# USB.net
KiCad netlist of a schematic drawn in Altium Designer
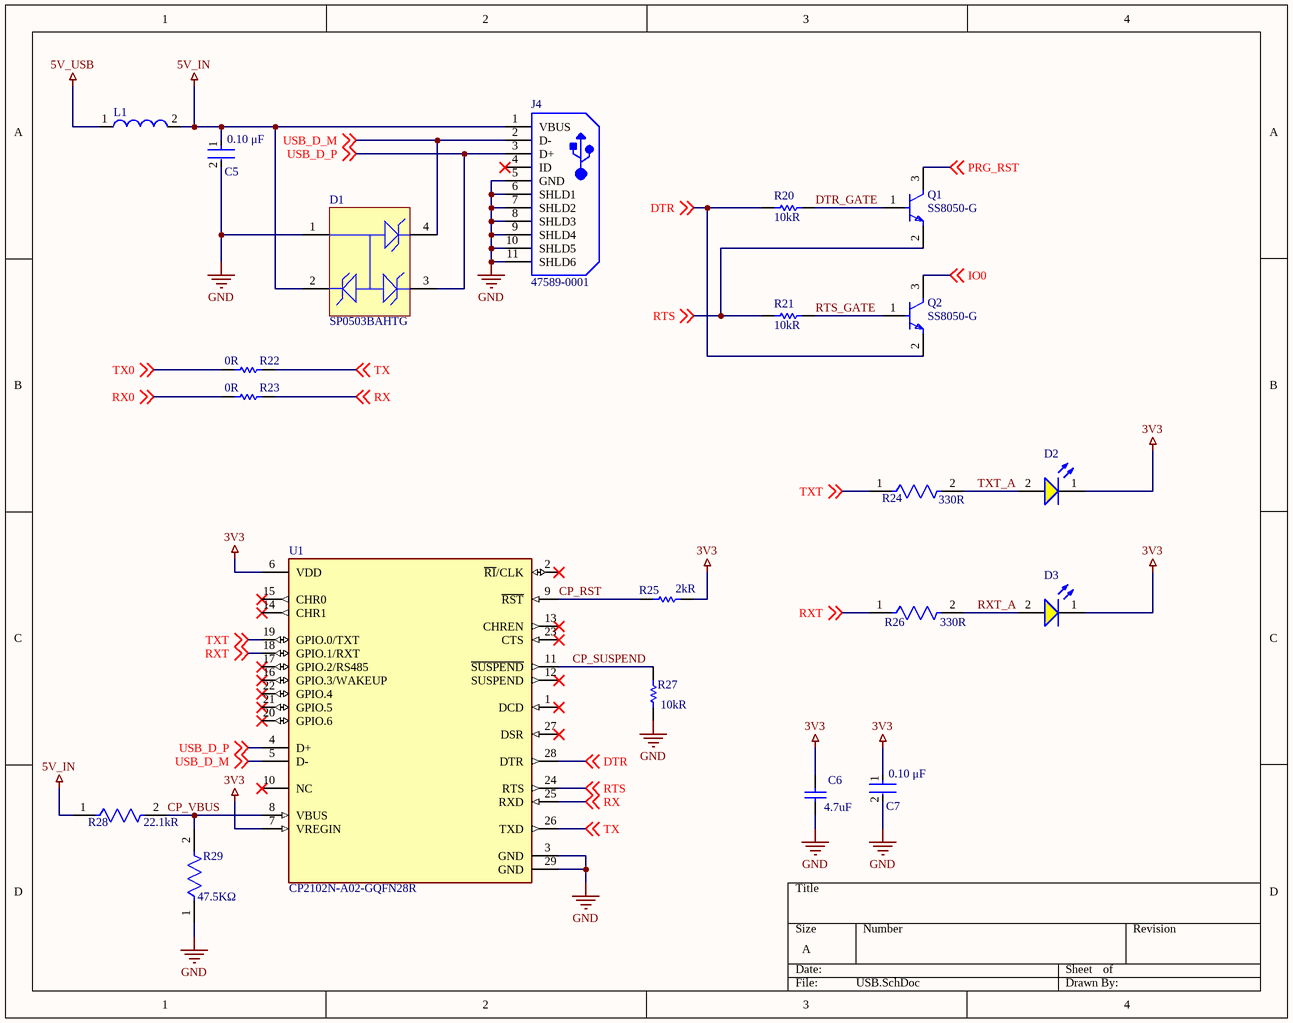
[diagram p0: USB.SchDoc]

(export (version "E")
  (design (tool "Eeschema 10.0.6"))
  (components
    (comp (ref "C5")
      (value "0.10 μF")
      (footprint "FP-C1206C-EB-MFG")
      (description "CAP CER 0.1UF 100V X7R 1206")
      (fields
        (field (name "TOLERANCE") "0.1")
        (field (name "OCTOPART") "https://octopart.com/c1206c104k1ractu-kemet-89521")
      )
      (libsource (lib "Altium Content Vault") (part "b4654b650e69147ec39a6b967a45e02"))
    )
    (comp (ref "C6")
      (value "4.7uF")
      (footprint "CAPC1210(3225)220_M")
      (description "CAP 4.7uF 25V ±10% 1210 (3225 Metric) Thickness 2.2mm SMD")
      (fields (field (name "TOLERANCE") "Â±10%") (field (name "MANUFACTURER") "KEMET"))
      (libsource (lib "Altium Content Vault") (part "CAP"))
    )
    (comp (ref "C7")
      (value "0.10 μF")
      (footprint "FP-C1206C-EB-MFG")
      (description "CAP CER 0.1UF 100V X7R 1206")
      (fields
        (field (name "TOLERANCE") "0.1")
        (field (name "OCTOPART") "https://octopart.com/c1206c104k1ractu-kemet-89521")
      )
      (libsource (lib "Altium Content Vault") (part "b4654b650e69147ec39a6b967a45e02"))
    )
    (comp (ref "D1")
      (value "SP0503BAHTG")
      (footprint "LFUS-SOT143-4_V")
      (description "TVS Diode Array, 30 pF, 30 KV, -40 to 85 degC, 4-Pin SOT143, RoHS, Tape and Reel")
      (fields (field (name "MANUFACTURER") "Littelfuse"))
      (libsource (lib "Altium Content Vault") (part "LFUS-SP0503BAHTG-SOT143-4"))
    )
    (comp (ref "D2")
      (value "150080YS75000")
      (footprint "WL-SMCW_0805_150080xx75000")
      (fields (field (name "MANUFACTURER") "Wurth Electronics"))
      (libsource (lib "Altium Content Vault") (part "LED_Yellow_2A-1K"))
    )
    (comp (ref "D3")
      (value "150080YS75000")
      (footprint "WL-SMCW_0805_150080xx75000")
      (fields (field (name "MANUFACTURER") "Wurth Electronics"))
      (libsource (lib "Altium Content Vault") (part "LED_Yellow_2A-1K"))
    )
    (comp (ref "J4")
      (value "47589-0001")
      (footprint "MOLX-47589-0001_V")
      (description "Right Angle Female Type AB Micro USB Connector, 30 V, 1.8 A, -30 to 85 degC, RoHS, Tape and Reel")
      (fields (field (name "MANUFACTURER") "Molex"))
      (libsource (lib "Altium Content Vault") (part "USB-5-6SHLD"))
    )
    (comp (ref "L1")
      (value "742792093")
      (footprint "SMD-0805")
      (description "SMD EMI Suppression Ferrite Bead WE-CBF, Z = 2200 Ohm")
      (fields (field (name "MANUFACTURER") "Wurth Electronics"))
      (libsource (lib "Altium Content Vault") (part "PAS-IND-INDUCTOR-2"))
    )
    (comp (ref "Q1")
      (value "SS8050-G")
      (footprint "FP-SS8050-G-MFG")
      (description "NPN TRANSISTOR 1.5A 40V SOT-23 R")
      (libsource (lib "Altium Content Vault") (part "2a1388f82443b098dcd57d24ac7632d"))
    )
    (comp (ref "Q2")
      (value "SS8050-G")
      (footprint "FP-SS8050-G-MFG")
      (description "NPN TRANSISTOR 1.5A 40V SOT-23 R")
      (libsource (lib "Altium Content Vault") (part "2a1388f82443b098dcd57d24ac7632d"))
    )
    (comp (ref "R20")
      (value "10kR")
      (footprint "RESC2013X60X35NL10T20")
      (description "Chip Resistor, 10 KOhm, +/- 1%, 0.125 W, -55 to 155 degC, 0805 (2012 Metric), RoHS, Tape and Reel")
      (fields
        (field (name "MANUFACTURER") "Yageo")
        (field (name "MANUFACTURER PART NUMBER") "RC0805FR-0710KL")
      )
      (libsource (lib "Altium Content Vault") (part "RES-2"))
    )
    (comp (ref "R21")
      (value "10kR")
      (footprint "RESC2013X60X35NL10T20")
      (description "Chip Resistor, 10 KOhm, +/- 1%, 0.125 W, -55 to 155 degC, 0805 (2012 Metric), RoHS, Tape and Reel")
      (fields
        (field (name "MANUFACTURER") "Yageo")
        (field (name "MANUFACTURER PART NUMBER") "RC0805FR-0710KL")
      )
      (libsource (lib "Altium Content Vault") (part "RES-2"))
    )
    (comp (ref "R22")
      (value "0R")
      (footprint "RESC2013X50X30LL20T20")
      (fields
        (field (name "MANUFACTURER") "Vishay Dale")
        (field (name "PART NUMBER") "CRCW08050000Z0EA")
        (field (name "POWER") "125mW")
      )
      (libsource (lib "Altium Content Vault") (part "RES"))
    )
    (comp (ref "R23")
      (value "0R")
      (footprint "RESC2013X50X30LL20T20")
      (fields
        (field (name "MANUFACTURER") "Vishay Dale")
        (field (name "PART NUMBER") "CRCW08050000Z0EA")
        (field (name "POWER") "125mW")
      )
      (libsource (lib "Altium Content Vault") (part "RES"))
    )
    (comp (ref "R24")
      (value "CRCW0805330RFKEA")
      (footprint "FP-CRCW0805-e3-MFG")
      (description "RES Thick Film, 330Ω, 1%, 0.125W, 100ppm/°C, 0805")
      (fields
        (field (name "RESISTANCE") "330R")
        (field (name "TOLERANCE") "1%")
        (field (name "MANUFACTURER") "Vishay")
      )
      (libsource (lib "Altium Content Vault") (part "1029c3af85768c4190bb7ad29bc67b5"))
    )
    (comp (ref "R25")
      (value "2kR")
      (footprint "RESC3216X50X50LL20T25")
      (fields
        (field (name "PART NUMBER") "RG3216P-2001-B-T1")
        (field (name "MANUFACTURER") "Susumu")
        (field (name "TOLERANCE") "0.1%")
      )
      (libsource (lib "Altium Content Vault") (part "RES"))
    )
    (comp (ref "R26")
      (value "CRCW0805330RFKEA")
      (footprint "FP-CRCW0805-e3-MFG")
      (description "RES Thick Film, 330Ω, 1%, 0.125W, 100ppm/°C, 0805")
      (fields
        (field (name "RESISTANCE") "330R")
        (field (name "TOLERANCE") "1%")
        (field (name "MANUFACTURER") "Vishay")
      )
      (libsource (lib "Altium Content Vault") (part "1029c3af85768c4190bb7ad29bc67b5"))
    )
    (comp (ref "R27")
      (value "10kR")
      (footprint "RESC2013X60X35NL10T20")
      (description "Chip Resistor, 10 KOhm, +/- 1%, 0.125 W, -55 to 155 degC, 0805 (2012 Metric), RoHS, Tape and Reel")
      (fields
        (field (name "MANUFACTURER") "Yageo")
        (field (name "MANUFACTURER PART NUMBER") "RC0805FR-0710KL")
      )
      (libsource (lib "Altium Content Vault") (part "RES-2"))
    )
    (comp (ref "R28")
      (value "RMCF0805FT22K1")
      (footprint "FP-RMCF0805-IPC_B")
      (description "22.1kΩ ±1% 0.125W 0805 Thick Film Chip Resistor AEC-Q200 compliant")
      (fields
        (field (name "RESISTANCE") "22.1kR")
        (field (name "TOLERANCE") "1%")
        (field (name "MANUFACTURER") "Stackpole Electronics")
      )
      (libsource (lib "Altium Content Vault") (part "1029c3af85768c4190bb7ad29bc67b5"))
    )
    (comp (ref "R29")
      (value "47.5KΩ")
      (footprint "FP-RN732A-MFG")
      (description "SMD Chip Resistor, Thin Film, 47.5KΩ, 100 V, 0805 [2012 Metric], 100 mW, 0.1%, RN73 Series")
      (fields
        (field (name "MANUFACTURER PART NUMBER") "RN73C2A47K5BTD")
        (field (name "MANUFACTURER") "TE Connectivity")
      )
      (libsource (lib "Altium Content Vault") (part "1029c3af85768c4190bb7ad29bc67b5"))
    )
    (comp (ref "U1")
      (value "CP2102N-A02-GQFN28R")
      (footprint "FP-CP2102N-A02-GQFN28R-MFG")
      (description "IC USB TO UART BRIDGE QFN28")
      (libsource (lib "Altium Content Vault") (part "670edaef084fb69d2a747396d70a05e"))
    )
  )
  (nets
    (net (code "1") (name "/CP_RST") (class "Default")
      (node (ref "R25") (pin "1") (pinfunction "1_1") (pintype "passive"))
      (node (ref "U1") (pin "9") (pinfunction "~{RST}_9") (pintype "input"))
    )
    (net (code "2") (name "/CP_SUSPEND") (class "Default")
      (node (ref "R27") (pin "2") (pinfunction "2_2") (pintype "passive"))
      (node (ref "U1") (pin "11") (pinfunction "~{SUSPEND}_11") (pintype "output"))
    )
    (net (code "3") (name "/CP_VBUS") (class "Default")
      (node (ref "R28") (pin "2") (pinfunction "2_2") (pintype "passive"))
      (node (ref "R29") (pin "2") (pinfunction "2_2") (pintype "passive"))
      (node (ref "U1") (pin "8") (pinfunction "VBUS_8") (pintype "input"))
    )
    (net (code "4") (name "/DTR_GATE") (class "Default")
      (node (ref "Q1") (pin "1") (pinfunction "B_1") (pintype "passive"))
      (node (ref "R20") (pin "2") (pinfunction "2_2") (pintype "passive"))
    )
    (net (code "5") (name "/RTS_GATE") (class "Default")
      (node (ref "Q2") (pin "1") (pinfunction "B_1") (pintype "passive"))
      (node (ref "R21") (pin "1") (pinfunction "1_1") (pintype "passive"))
    )
    (net (code "6") (name "/RXT_A") (class "Default")
      (node (ref "D3") (pin "2") (pinfunction "A_2") (pintype "passive"))
      (node (ref "R26") (pin "2") (pinfunction "2_2") (pintype "passive"))
    )
    (net (code "7") (name "/TXT_A") (class "Default")
      (node (ref "D2") (pin "2") (pinfunction "A_2") (pintype "passive"))
      (node (ref "R24") (pin "2") (pinfunction "2_2") (pintype "passive"))
    )
    (net (code "8") (name "3V3") (class "Default")
      (node (ref "C6") (pin "2") (pinfunction "2_2") (pintype "passive"))
      (node (ref "C7") (pin "1") (pinfunction "1_1") (pintype "passive"))
      (node (ref "D2") (pin "1") (pinfunction "K_1") (pintype "passive"))
      (node (ref "D3") (pin "1") (pinfunction "K_1") (pintype "passive"))
      (node (ref "R25") (pin "2") (pinfunction "2_2") (pintype "passive"))
      (node (ref "U1") (pin "6") (pinfunction "VDD_6") (pintype "power_in"))
      (node (ref "U1") (pin "7") (pinfunction "VREGIN_7") (pintype "input"))
    )
    (net (code "9") (name "5V_IN") (class "Default")
      (node (ref "C5") (pin "1") (pinfunction "1_1") (pintype "passive"))
      (node (ref "D1") (pin "2") (pinfunction "2_2") (pintype "passive"))
      (node (ref "J4") (pin "1") (pinfunction "VBUS_1") (pintype "passive"))
      (node (ref "L1") (pin "2") (pinfunction "2_2") (pintype "passive"))
      (node (ref "R28") (pin "1") (pinfunction "1_1") (pintype "passive"))
    )
    (net (code "10") (name "5V_USB") (class "Default")
      (node (ref "L1") (pin "1") (pinfunction "1_1") (pintype "passive"))
    )
    (net (code "11") (name "DTR") (class "Default")
      (node (ref "Q2") (pin "2") (pinfunction "E_2") (pintype "passive"))
      (node (ref "R20") (pin "1") (pinfunction "1_1") (pintype "passive"))
      (node (ref "U1") (pin "28") (pinfunction "DTR_28") (pintype "output"))
    )
    (net (code "12") (name "GND") (class "Default")
      (node (ref "C5") (pin "2") (pinfunction "2_2") (pintype "passive"))
      (node (ref "C6") (pin "1") (pinfunction "1_1") (pintype "passive"))
      (node (ref "C7") (pin "2") (pinfunction "2_2") (pintype "passive"))
      (node (ref "D1") (pin "1") (pinfunction "1_1") (pintype "passive"))
      (node (ref "J4") (pin "10") (pinfunction "SHLD5_10") (pintype "passive"))
      (node (ref "J4") (pin "11") (pinfunction "SHLD6_11") (pintype "passive"))
      (node (ref "J4") (pin "5") (pinfunction "GND_5") (pintype "passive"))
      (node (ref "J4") (pin "6") (pinfunction "SHLD1_6") (pintype "passive"))
      (node (ref "J4") (pin "7") (pinfunction "SHLD2_7") (pintype "passive"))
      (node (ref "J4") (pin "8") (pinfunction "SHLD3_8") (pintype "passive"))
      (node (ref "J4") (pin "9") (pinfunction "SHLD4_9") (pintype "passive"))
      (node (ref "R27") (pin "1") (pinfunction "1_1") (pintype "passive"))
      (node (ref "R29") (pin "1") (pinfunction "1_1") (pintype "passive"))
      (node (ref "U1") (pin "29") (pinfunction "GND_29") (pintype "power_in"))
      (node (ref "U1") (pin "3") (pinfunction "GND_3") (pintype "power_in"))
    )
    (net (code "13") (name "IO0") (class "Default")
      (node (ref "Q2") (pin "3") (pinfunction "C_3") (pintype "passive"))
    )
    (net (code "14") (name "PRG_RST") (class "Default")
      (node (ref "Q1") (pin "3") (pinfunction "C_3") (pintype "passive"))
    )
    (net (code "15") (name "RTS") (class "Default")
      (node (ref "Q1") (pin "2") (pinfunction "E_2") (pintype "passive"))
      (node (ref "R21") (pin "2") (pinfunction "2_2") (pintype "passive"))
      (node (ref "U1") (pin "24") (pinfunction "RTS_24") (pintype "output"))
    )
    (net (code "16") (name "RX") (class "Default")
      (node (ref "R23") (pin "2") (pinfunction "2_2") (pintype "passive"))
      (node (ref "U1") (pin "25") (pinfunction "RXD_25") (pintype "input"))
    )
    (net (code "17") (name "RX0") (class "Default")
      (node (ref "R23") (pin "1") (pinfunction "1_1") (pintype "passive"))
    )
    (net (code "18") (name "RXT") (class "Default")
      (node (ref "R26") (pin "1") (pinfunction "1_1") (pintype "passive"))
      (node (ref "U1") (pin "18") (pinfunction "GPIO.1/RXT_18") (pintype "bidirectional"))
    )
    (net (code "19") (name "TX") (class "Default")
      (node (ref "R22") (pin "2") (pinfunction "2_2") (pintype "passive"))
      (node (ref "U1") (pin "26") (pinfunction "TXD_26") (pintype "output"))
    )
    (net (code "20") (name "TX0") (class "Default")
      (node (ref "R22") (pin "1") (pinfunction "1_1") (pintype "passive"))
    )
    (net (code "21") (name "TXT") (class "Default")
      (node (ref "R24") (pin "1") (pinfunction "1_1") (pintype "passive"))
      (node (ref "U1") (pin "19") (pinfunction "GPIO.0/TXT_19") (pintype "bidirectional"))
    )
    (net (code "22") (name "USB_D_M") (class "Default")
      (node (ref "D1") (pin "4") (pinfunction "4_4") (pintype "passive"))
      (node (ref "J4") (pin "2") (pinfunction "D-_2") (pintype "passive"))
      (node (ref "U1") (pin "5") (pinfunction "D-_5") (pintype "passive"))
    )
    (net (code "23") (name "USB_D_P") (class "Default")
      (node (ref "D1") (pin "3") (pinfunction "3_3") (pintype "passive"))
      (node (ref "J4") (pin "3") (pinfunction "D+_3") (pintype "passive"))
      (node (ref "U1") (pin "4") (pinfunction "D+_4") (pintype "passive"))
    )
    (net (code "24") (name "unconnected-(J4-ID-Pad4)") (class "Default")
      (node (ref "J4") (pin "4") (pinfunction "ID_4") (pintype "passive+no_connect"))
    )
    (net (code "25") (name "unconnected-(U1-CHR0-Pad15)") (class "Default")
      (node (ref "U1") (pin "15") (pinfunction "CHR0_15") (pintype "output+no_connect"))
    )
    (net (code "26") (name "unconnected-(U1-CHR1-Pad14)") (class "Default")
      (node (ref "U1") (pin "14") (pinfunction "CHR1_14") (pintype "output+no_connect"))
    )
    (net (code "27") (name "unconnected-(U1-CHREN-Pad13)") (class "Default")
      (node (ref "U1") (pin "13") (pinfunction "CHREN_13") (pintype "output+no_connect"))
    )
    (net (code "28") (name "unconnected-(U1-CTS-Pad23)") (class "Default")
      (node (ref "U1") (pin "23") (pinfunction "CTS_23") (pintype "input+no_connect"))
    )
    (net (code "29") (name "unconnected-(U1-DCD-Pad1)") (class "Default")
      (node (ref "U1") (pin "1") (pinfunction "DCD_1") (pintype "input+no_connect"))
    )
    (net (code "30") (name "unconnected-(U1-DSR-Pad27)") (class "Default")
      (node (ref "U1") (pin "27") (pinfunction "DSR_27") (pintype "input+no_connect"))
    )
    (net (code "31") (name "unconnected-(U1-GPIO.2{slash}RS485-Pad17)") (class "Default")
      (node (ref "U1") (pin "17") (pinfunction "GPIO.2/RS485_17") (pintype "bidirectional+no_connect"))
    )
    (net (code "32") (name "unconnected-(U1-GPIO.3{slash}WAKEUP-Pad16)") (class "Default")
      (node (ref "U1") (pin "16") (pinfunction "GPIO.3/WAKEUP_16") (pintype "bidirectional+no_connect"))
    )
    (net (code "33") (name "unconnected-(U1-GPIO.4-Pad22)") (class "Default")
      (node (ref "U1") (pin "22") (pinfunction "GPIO.4_22") (pintype "bidirectional+no_connect"))
    )
    (net (code "34") (name "unconnected-(U1-GPIO.5-Pad21)") (class "Default")
      (node (ref "U1") (pin "21") (pinfunction "GPIO.5_21") (pintype "bidirectional+no_connect"))
    )
    (net (code "35") (name "unconnected-(U1-GPIO.6-Pad20)") (class "Default")
      (node (ref "U1") (pin "20") (pinfunction "GPIO.6_20") (pintype "bidirectional+no_connect"))
    )
    (net (code "36") (name "unconnected-(U1-NC-Pad10)") (class "Default")
      (node (ref "U1") (pin "10") (pinfunction "NC_10") (pintype "passive+no_connect"))
    )
    (net (code "37") (name "unconnected-(U1-SUSPEND-Pad12)") (class "Default")
      (node (ref "U1") (pin "12") (pinfunction "SUSPEND_12") (pintype "output+no_connect"))
    )
    (net (code "38") (name "unconnected-(U1-~{RI}{slash}CLK-Pad2)") (class "Default")
      (node (ref "U1") (pin "2") (pinfunction "~{RI}/CLK_2") (pintype "bidirectional+no_connect"))
    )
  )
)
